# d_enc_v2.net
KiCad netlist of a schematic drawn in EAGLE
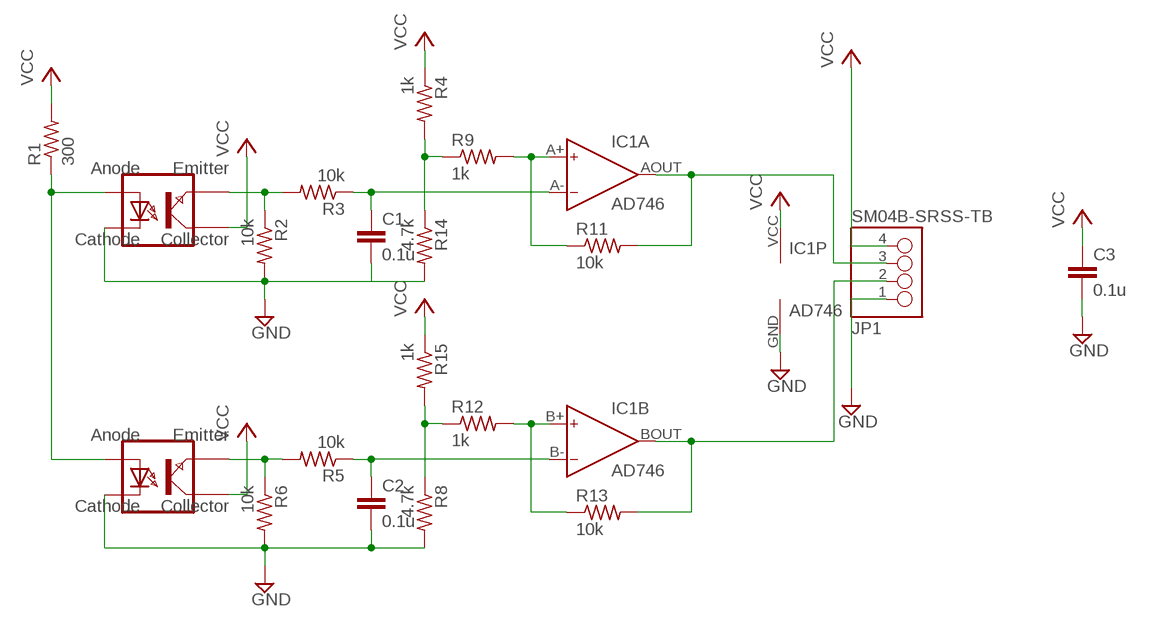
[diagram p0: schematic, sheet 1]

(export (version "E")
  (design (tool "Eeschema 10.0.6"))
  (components
    (comp (ref "C1")
      (value "0.1u")
      (footprint "eagle-import:C0603")
      (libsource (lib "eagle-import") (part "C-EUC0603"))
    )
    (comp (ref "C2")
      (value "0.1u")
      (footprint "eagle-import:C0603")
      (libsource (lib "eagle-import") (part "C-EUC0603"))
    )
    (comp (ref "C3")
      (value "0.1u")
      (footprint "eagle-import:C0603")
      (libsource (lib "eagle-import") (part "C-EUC0603"))
    )
    (comp (ref "IC1")
      (value "AD746")
      (footprint "eagle-import:NJM2903E")
      (libsource (lib "eagle-import") (part "AD746"))
    )
    (comp (ref "JP1")
      (value "SM04B-SRSS-TB")
      (footprint "eagle-import:SM04B-SRSS-TB")
      (libsource (lib "eagle-import") (part "SM04B-SRSS-TB"))
    )
    (comp (ref "R1")
      (value "300")
      (footprint "eagle-import:R0603")
      (libsource (lib "eagle-import") (part "R-US_R0603"))
    )
    (comp (ref "R2")
      (value "10k")
      (footprint "eagle-import:R0603")
      (libsource (lib "eagle-import") (part "R-US_R0603"))
    )
    (comp (ref "R3")
      (value "10k")
      (footprint "eagle-import:R0603")
      (libsource (lib "eagle-import") (part "R-US_R0603"))
    )
    (comp (ref "R4")
      (value "1k")
      (footprint "eagle-import:R0603")
      (libsource (lib "eagle-import") (part "R-US_R0603"))
    )
    (comp (ref "R5")
      (value "10k")
      (footprint "eagle-import:R0603")
      (libsource (lib "eagle-import") (part "R-US_R0603"))
    )
    (comp (ref "R6")
      (value "10k")
      (footprint "eagle-import:R0603")
      (libsource (lib "eagle-import") (part "R-US_R0603"))
    )
    (comp (ref "R8")
      (value "4.7k")
      (footprint "eagle-import:R0603")
      (libsource (lib "eagle-import") (part "R-US_R0603"))
    )
    (comp (ref "R9")
      (value "1k")
      (footprint "eagle-import:R0603")
      (libsource (lib "eagle-import") (part "R-US_R0603"))
    )
    (comp (ref "R11")
      (value "10k")
      (footprint "eagle-import:R0603")
      (libsource (lib "eagle-import") (part "R-US_R0603"))
    )
    (comp (ref "R12")
      (value "1k")
      (footprint "eagle-import:R0603")
      (libsource (lib "eagle-import") (part "R-US_R0603"))
    )
    (comp (ref "R13")
      (value "10k")
      (footprint "eagle-import:R0603")
      (libsource (lib "eagle-import") (part "R-US_R0603"))
    )
    (comp (ref "R14")
      (value "4.7k")
      (footprint "eagle-import:R0603")
      (libsource (lib "eagle-import") (part "R-US_R0603"))
    )
    (comp (ref "R15")
      (value "1k")
      (footprint "eagle-import:R0603")
      (libsource (lib "eagle-import") (part "R-US_R0603"))
    )
    (comp (ref "U$1")
      (value "TPR-105F")
      (footprint "eagle-import:TPR-105F")
      (libsource (lib "eagle-import") (part "TPR-105F"))
    )
    (comp (ref "U$4")
      (value "TPR-105F")
      (footprint "eagle-import:TPR-105F")
      (libsource (lib "eagle-import") (part "TPR-105F"))
    )
  )
  (nets
    (net (code "1") (name "GND") (class "Default")
      (node (ref "C1") (pin "2") (pinfunction "2_2") (pintype "passive"))
      (node (ref "C2") (pin "2") (pinfunction "2_2") (pintype "passive"))
      (node (ref "C3") (pin "2") (pinfunction "2_2") (pintype "passive"))
      (node (ref "IC1") (pin "GND") (pinfunction "V-_GND") (pintype "power_in"))
      (node (ref "JP1") (pin "1") (pinfunction "P$1_1") (pintype "bidirectional"))
      (node (ref "R14") (pin "2") (pinfunction "2_2") (pintype "passive"))
      (node (ref "R2") (pin "2") (pinfunction "2_2") (pintype "passive"))
      (node (ref "R6") (pin "2") (pinfunction "2_2") (pintype "passive"))
      (node (ref "R8") (pin "2") (pinfunction "2_2") (pintype "passive"))
      (node (ref "U$1") (pin "CATHODE") (pinfunction "CATHODE_CATHODE") (pintype "bidirectional"))
      (node (ref "U$4") (pin "CATHODE") (pinfunction "CATHODE_CATHODE") (pintype "bidirectional"))
    )
    (net (code "2") (name "Net-(IC1A-IN+)") (class "Default")
      (node (ref "IC1") (pin "A+") (pinfunction "IN+_A+") (pintype "input"))
      (node (ref "R11") (pin "1") (pinfunction "1_1") (pintype "passive"))
      (node (ref "R9") (pin "2") (pinfunction "2_2") (pintype "passive"))
    )
    (net (code "3") (name "Net-(IC1A-IN-)") (class "Default")
      (node (ref "C1") (pin "1") (pinfunction "1_1") (pintype "passive"))
      (node (ref "IC1") (pin "A-") (pinfunction "IN-_A-") (pintype "input"))
      (node (ref "R3") (pin "1") (pinfunction "1_1") (pintype "passive"))
    )
    (net (code "4") (name "Net-(IC1A-OUT)") (class "Default")
      (node (ref "IC1") (pin "AOUT") (pinfunction "OUT_AOUT") (pintype "output"))
      (node (ref "JP1") (pin "3") (pinfunction "P$3_3") (pintype "bidirectional"))
      (node (ref "R11") (pin "2") (pinfunction "2_2") (pintype "passive"))
    )
    (net (code "5") (name "Net-(IC1B-IN+)") (class "Default")
      (node (ref "IC1") (pin "B+") (pinfunction "IN+_B+") (pintype "input"))
      (node (ref "R12") (pin "2") (pinfunction "2_2") (pintype "passive"))
      (node (ref "R13") (pin "1") (pinfunction "1_1") (pintype "passive"))
    )
    (net (code "6") (name "Net-(IC1B-IN-)") (class "Default")
      (node (ref "C2") (pin "1") (pinfunction "1_1") (pintype "passive"))
      (node (ref "IC1") (pin "B-") (pinfunction "IN-_B-") (pintype "input"))
      (node (ref "R5") (pin "1") (pinfunction "1_1") (pintype "passive"))
    )
    (net (code "7") (name "Net-(IC1B-OUT)") (class "Default")
      (node (ref "IC1") (pin "BOUT") (pinfunction "OUT_BOUT") (pintype "output"))
      (node (ref "JP1") (pin "2") (pinfunction "P$2_2") (pintype "bidirectional"))
      (node (ref "R13") (pin "2") (pinfunction "2_2") (pintype "passive"))
    )
    (net (code "8") (name "Net-(R1-Pad1)") (class "Default")
      (node (ref "R1") (pin "1") (pinfunction "1_1") (pintype "passive"))
      (node (ref "U$1") (pin "ANODE") (pinfunction "ANODE_ANODE") (pintype "bidirectional"))
      (node (ref "U$4") (pin "ANODE") (pinfunction "ANODE_ANODE") (pintype "bidirectional"))
    )
    (net (code "9") (name "Net-(R2-Pad1)") (class "Default")
      (node (ref "R2") (pin "1") (pinfunction "1_1") (pintype "passive"))
      (node (ref "R3") (pin "2") (pinfunction "2_2") (pintype "passive"))
      (node (ref "U$4") (pin "EMITTER") (pinfunction "EMITTER_EMITTER") (pintype "bidirectional"))
    )
    (net (code "10") (name "Net-(R5-Pad2)") (class "Default")
      (node (ref "R5") (pin "2") (pinfunction "2_2") (pintype "passive"))
      (node (ref "R6") (pin "1") (pinfunction "1_1") (pintype "passive"))
      (node (ref "U$1") (pin "EMITTER") (pinfunction "EMITTER_EMITTER") (pintype "bidirectional"))
    )
    (net (code "11") (name "Net-(R12-Pad1)") (class "Default")
      (node (ref "R12") (pin "1") (pinfunction "1_1") (pintype "passive"))
      (node (ref "R15") (pin "2") (pinfunction "2_2") (pintype "passive"))
      (node (ref "R8") (pin "1") (pinfunction "1_1") (pintype "passive"))
    )
    (net (code "12") (name "Net-(R14-Pad1)") (class "Default")
      (node (ref "R14") (pin "1") (pinfunction "1_1") (pintype "passive"))
      (node (ref "R4") (pin "2") (pinfunction "2_2") (pintype "passive"))
      (node (ref "R9") (pin "1") (pinfunction "1_1") (pintype "passive"))
    )
    (net (code "13") (name "VCC") (class "Default")
      (node (ref "C3") (pin "1") (pinfunction "1_1") (pintype "passive"))
      (node (ref "IC1") (pin "VCC") (pinfunction "V+_VCC") (pintype "power_in"))
      (node (ref "JP1") (pin "4") (pinfunction "P$4_4") (pintype "bidirectional"))
      (node (ref "R1") (pin "2") (pinfunction "2_2") (pintype "passive"))
      (node (ref "R15") (pin "1") (pinfunction "1_1") (pintype "passive"))
      (node (ref "R4") (pin "1") (pinfunction "1_1") (pintype "passive"))
      (node (ref "U$1") (pin "COLLECTOR") (pinfunction "COLLECTOR_COLLECTOR") (pintype "bidirectional"))
      (node (ref "U$4") (pin "COLLECTOR") (pinfunction "COLLECTOR_COLLECTOR") (pintype "bidirectional"))
    )
  )
)
